# PD.net
KiCad netlist of a schematic drawn in Altium Designer
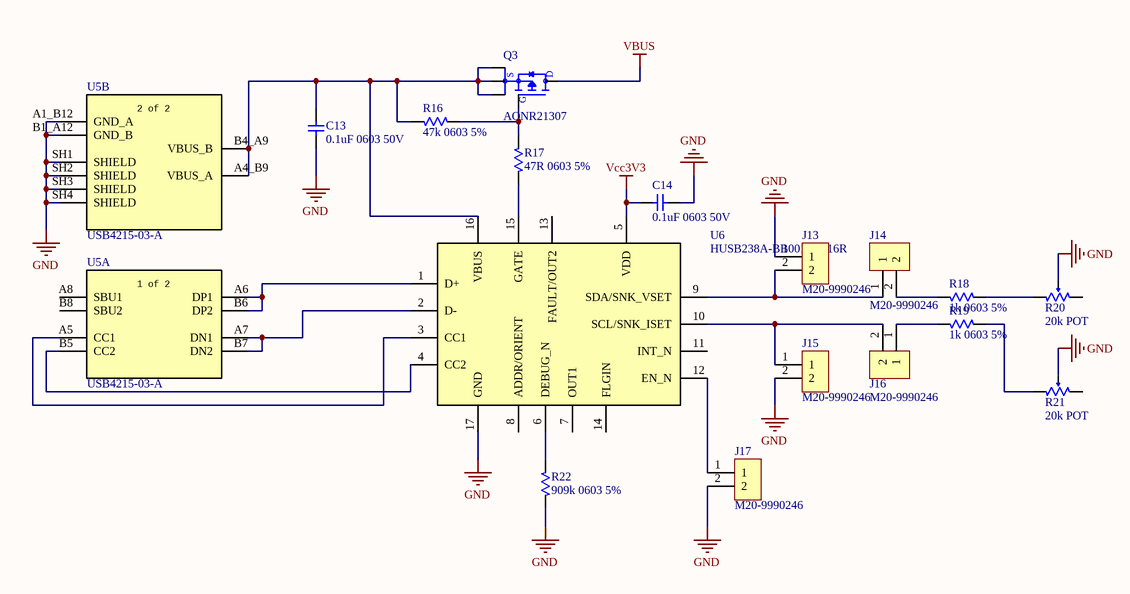
[diagram p0: PD.SchDoc]

(export (version "E")
  (design (tool "Eeschema 10.0.6"))
  (components
    (comp (ref "C13")
      (value "0.1uF 0603 50V")
      (footprint "CAP_0603")
      (description "50V 0.1uF (100nF) X7R ±10% 0603 Multilayer Ceramic Capacitors MLCC - SMD/SMT ROHS")
      (fields
        (field (name "MANUFACTURER PART NUMBER") "CL10B104KB8NNNC")
        (field (name "JLCPCB PART NUMBER") "C1591")
      )
      (libsource (lib "Amperry") (part "Capacitor"))
    )
    (comp (ref "C14")
      (value "0.1uF 0603 50V")
      (footprint "CAP_0603")
      (description "50V 0.1uF (100nF) X7R ±10% 0603 Multilayer Ceramic Capacitors MLCC - SMD/SMT ROHS")
      (fields
        (field (name "MANUFACTURER PART NUMBER") "CL10B104KB8NNNC")
        (field (name "JLCPCB PART NUMBER") "C1591")
      )
      (libsource (lib "Amperry") (part "Capacitor"))
    )
    (comp (ref "J13")
      (value "M20-9990246")
      (footprint "Header_Male_1x2_2.54mm")
      (description "Header Male 1x2 2.54mm")
      (fields (field (name "JLCPCB PART NUMBER") "C90288") (field (name "MANUFACTURER") "Harwin"))
      (libsource (lib "Amperry") (part "Header_Male_1x2"))
    )
    (comp (ref "J14")
      (value "M20-9990246")
      (footprint "Header_Male_1x2_2.54mm")
      (description "Header Male 1x2 2.54mm")
      (fields (field (name "JLCPCB PART NUMBER") "C90288") (field (name "MANUFACTURER") "Harwin"))
      (libsource (lib "") (part "Header_Male_1x2_1"))
    )
    (comp (ref "J15")
      (value "M20-9990246")
      (footprint "Header_Male_1x2_2.54mm")
      (description "Header Male 1x2 2.54mm")
      (fields (field (name "JLCPCB PART NUMBER") "C90288") (field (name "MANUFACTURER") "Harwin"))
      (libsource (lib "Amperry") (part "Header_Male_1x2"))
    )
    (comp (ref "J16")
      (value "M20-9990246")
      (footprint "Header_Male_1x2_2.54mm")
      (description "Header Male 1x2 2.54mm")
      (fields (field (name "JLCPCB PART NUMBER") "C90288") (field (name "MANUFACTURER") "Harwin"))
      (libsource (lib "") (part "Header_Male_1x2_2"))
    )
    (comp (ref "J17")
      (value "M20-9990246")
      (footprint "Header_Male_1x2_2.54mm")
      (description "Header Male 1x2 2.54mm")
      (fields (field (name "JLCPCB PART NUMBER") "C90288") (field (name "MANUFACTURER") "Harwin"))
      (libsource (lib "Amperry") (part "Header_Male_1x2"))
    )
    (comp (ref "Q3")
      (value "AONR21307")
      (footprint "DFN 3x3 EP")
      (description "P-CHANNEL MOSFET 30V 24A 8DFN")
      (fields
        (field (name "JLCPCB PART NUMBER") "C3277813")
        (field (name "MANUFACTURER") "Alpha & Omega Semiconductor")
      )
      (libsource (lib "Amperry") (part "AONR21307"))
    )
    (comp (ref "R16")
      (value "47k 0603 5%")
      (footprint "RES_0603")
      (description "47k Ohm 0603 5% Chip Resistor SMD")
      (fields (field (name "JLCPCB PART NUMBER") "C25819") (field (name "TOLERANCE") "5%"))
      (libsource (lib "Amperry") (part "Resistor"))
    )
    (comp (ref "R17")
      (value "47R 0603 5%")
      (footprint "RES_0603")
      (description "47 Ohm 0603 5% Chip Resistor SMD")
      (fields (field (name "TOLERANCE") "5%") (field (name "JLCPCB PART NUMBER") "C1186"))
      (libsource (lib "Amperry") (part "Resistor"))
    )
    (comp (ref "R18")
      (value "1k 0603 5%")
      (footprint "RES_0603")
      (description "1k 0603 5% Chip Resistor SMD")
      (fields (field (name "JLCPCB PART NUMBER") "C14676") (field (name "TOLERANCE") "5%"))
      (libsource (lib "Amperry") (part "Resistor"))
    )
    (comp (ref "R19")
      (value "1k 0603 5%")
      (footprint "RES_0603")
      (description "1k 0603 5% Chip Resistor SMD")
      (fields (field (name "JLCPCB PART NUMBER") "C14676") (field (name "TOLERANCE") "5%"))
      (libsource (lib "Amperry") (part "Resistor"))
    )
    (comp (ref "R20")
      (value "20k POT")
      (footprint "TRIM_3296W-1-203LF")
      (description "20k Ohm TH Trimmer Potentiometer")
      (fields (field (name "MANUFACTURER") "Bourns") (field (name "JLCPCB PART NUMBER") "C34845"))
      (libsource (lib "Amperry") (part "Resistor Variable"))
    )
    (comp (ref "R21")
      (value "20k POT")
      (footprint "TRIM_3296W-1-203LF")
      (description "20k Ohm TH Trimmer Potentiometer")
      (fields (field (name "MANUFACTURER") "Bourns") (field (name "JLCPCB PART NUMBER") "C34845"))
      (libsource (lib "Amperry") (part "Resistor Variable"))
    )
    (comp (ref "R22")
      (value "909k 0603 5%")
      (footprint "RES_0603")
      (description "909k Ohm 0603 1% Chip Resistor SMD")
      (fields
        (field (name "MANUFACTURER PART NUMBER") "0603WAF9093T5E")
        (field (name "JLCPCB PART NUMBER") "C23262")
      )
      (libsource (lib "Amperry") (part "Resistor"))
    )
    (comp (ref "U5")
      (value "USB4215-03-A")
      (footprint "USB4215-03-A")
      (description "USB-C, 12+4 Contacts 16POS Rohs Compliant: Yes")
      (fields
        (field (name "JLCPCB PART NUMBER") "C165948")
        (field (name "MANUFACTURER") "Global Connector Technology")
      )
      (libsource (lib "Amperry") (part "USB-C 16P"))
    )
    (comp (ref "U6")
      (value "HUSB238A-BB001-QN16R")
      (footprint "QFN-16")
      (description "USB PD Controller")
      (fields (field (name "JLCPCB PART NUMBER") "C24833806"))
      (libsource (lib "Amperry") (part "HUSB238A-BB001-QN16R"))
    )
  )
  (nets
    (net (code "1") (name "GND") (class "Default")
      (node (ref "C13") (pin "1") (pinfunction "1_1") (pintype "passive"))
      (node (ref "C14") (pin "2") (pinfunction "2_2") (pintype "passive"))
      (node (ref "J13") (pin "1") (pinfunction "1_1") (pintype "passive"))
      (node (ref "J15") (pin "2") (pinfunction "2_2") (pintype "passive"))
      (node (ref "J17") (pin "2") (pinfunction "2_2") (pintype "passive"))
      (node (ref "R20") (pin "2") (pinfunction "2_2") (pintype "passive"))
      (node (ref "R21") (pin "2") (pinfunction "2_2") (pintype "passive"))
      (node (ref "R22") (pin "1") (pinfunction "1_1") (pintype "passive"))
      (node (ref "U5") (pin "A1_B12") (pinfunction "GND_A_A1_B12") (pintype "power_in"))
      (node (ref "U5") (pin "B1_A12") (pinfunction "GND_B_B1_A12") (pintype "power_in"))
      (node (ref "U5") (pin "SH1") (pinfunction "SHIELD_SH1") (pintype "passive"))
      (node (ref "U5") (pin "SH2") (pinfunction "SHIELD_SH2") (pintype "passive"))
      (node (ref "U5") (pin "SH3") (pinfunction "SHIELD_SH3") (pintype "passive"))
      (node (ref "U5") (pin "SH4") (pinfunction "SHIELD_SH4") (pintype "passive"))
      (node (ref "U6") (pin "17") (pinfunction "GND_17") (pintype "passive"))
    )
    (net (code "2") (name "Net-(J14-Pad2)") (class "Default")
      (node (ref "J14") (pin "2") (pinfunction "2_2") (pintype "passive"))
      (node (ref "R18") (pin "1") (pinfunction "1_1") (pintype "passive"))
    )
    (net (code "3") (name "Net-(J16-Pad1)") (class "Default")
      (node (ref "J16") (pin "1") (pinfunction "1_1") (pintype "passive"))
      (node (ref "R19") (pin "1") (pinfunction "1_1") (pintype "passive"))
    )
    (net (code "4") (name "Net-(Q3-G)") (class "Default")
      (node (ref "Q3") (pin "4") (pinfunction "G_4") (pintype "passive"))
      (node (ref "R16") (pin "2") (pinfunction "2_2") (pintype "passive"))
      (node (ref "R17") (pin "2") (pinfunction "2_2") (pintype "passive"))
    )
    (net (code "5") (name "Net-(Q3-S1)") (class "Default")
      (node (ref "C13") (pin "2") (pinfunction "2_2") (pintype "passive"))
      (node (ref "Q3") (pin "1") (pinfunction "S1_1") (pintype "passive"))
      (node (ref "Q3") (pin "2") (pinfunction "S2_2") (pintype "passive"))
      (node (ref "Q3") (pin "3") (pinfunction "S3_3") (pintype "passive"))
      (node (ref "R16") (pin "1") (pinfunction "1_1") (pintype "passive"))
      (node (ref "U5") (pin "A4_B9") (pinfunction "VBUS_A_A4_B9") (pintype "power_in"))
      (node (ref "U5") (pin "B4_A9") (pinfunction "VBUS_B_B4_A9") (pintype "power_in"))
      (node (ref "U6") (pin "16") (pinfunction "VBUS_16") (pintype "passive"))
    )
    (net (code "6") (name "Net-(R18-Pad2)") (class "Default")
      (node (ref "R18") (pin "2") (pinfunction "2_2") (pintype "passive"))
      (node (ref "R20") (pin "1") (pinfunction "1_1") (pintype "passive"))
    )
    (net (code "7") (name "Net-(R19-Pad2)") (class "Default")
      (node (ref "R19") (pin "2") (pinfunction "2_2") (pintype "passive"))
      (node (ref "R21") (pin "1") (pinfunction "1_1") (pintype "passive"))
    )
    (net (code "8") (name "Net-(U5A-CC1)") (class "Default")
      (node (ref "U5") (pin "A5") (pinfunction "CC1_A5") (pintype "passive"))
      (node (ref "U6") (pin "3") (pinfunction "CC1_3") (pintype "passive"))
    )
    (net (code "9") (name "Net-(U5A-CC2)") (class "Default")
      (node (ref "U5") (pin "B5") (pinfunction "CC2_B5") (pintype "passive"))
      (node (ref "U6") (pin "4") (pinfunction "CC2_4") (pintype "passive"))
    )
    (net (code "10") (name "Net-(U5A-DN1)") (class "Default")
      (node (ref "U5") (pin "A7") (pinfunction "DN1_A7") (pintype "passive"))
      (node (ref "U5") (pin "B7") (pinfunction "DN2_B7") (pintype "passive"))
      (node (ref "U6") (pin "2") (pinfunction "D-_2") (pintype "passive"))
    )
    (net (code "11") (name "Net-(U5A-DP1)") (class "Default")
      (node (ref "U5") (pin "A6") (pinfunction "DP1_A6") (pintype "passive"))
      (node (ref "U5") (pin "B6") (pinfunction "DP2_B6") (pintype "passive"))
      (node (ref "U6") (pin "1") (pinfunction "D+_1") (pintype "passive"))
    )
    (net (code "12") (name "Net-(U6-DEBUG_N)") (class "Default")
      (node (ref "R22") (pin "2") (pinfunction "2_2") (pintype "passive"))
      (node (ref "U6") (pin "6") (pinfunction "DEBUG_N_6") (pintype "passive"))
    )
    (net (code "13") (name "Net-(U6-EN_N)") (class "Default")
      (node (ref "J17") (pin "1") (pinfunction "1_1") (pintype "passive"))
      (node (ref "U6") (pin "12") (pinfunction "EN_N_12") (pintype "passive"))
    )
    (net (code "14") (name "Net-(U6-GATE)") (class "Default")
      (node (ref "R17") (pin "1") (pinfunction "1_1") (pintype "passive"))
      (node (ref "U6") (pin "15") (pinfunction "GATE_15") (pintype "passive"))
    )
    (net (code "15") (name "Net-(U6-SCL{slash}SNK_ISET)") (class "Default")
      (node (ref "J15") (pin "1") (pinfunction "1_1") (pintype "passive"))
      (node (ref "J16") (pin "2") (pinfunction "2_2") (pintype "passive"))
      (node (ref "U6") (pin "10") (pinfunction "SCL/SNK_ISET_10") (pintype "passive"))
    )
    (net (code "16") (name "Net-(U6-SDA{slash}SNK_VSET)") (class "Default")
      (node (ref "J13") (pin "2") (pinfunction "2_2") (pintype "passive"))
      (node (ref "J14") (pin "1") (pinfunction "1_1") (pintype "passive"))
      (node (ref "U6") (pin "9") (pinfunction "SDA/SNK_VSET_9") (pintype "passive"))
    )
    (net (code "17") (name "VBUS") (class "Default")
      (node (ref "Q3") (pin "5_6_7_8") (pinfunction "D_5_6_7_8") (pintype "passive"))
    )
    (net (code "18") (name "Vcc3V3") (class "Default")
      (node (ref "C14") (pin "1") (pinfunction "1_1") (pintype "passive"))
      (node (ref "U6") (pin "5") (pinfunction "VDD_5") (pintype "passive"))
    )
    (net (code "19") (name "unconnected-(R20-Pad3)") (class "Default")
      (node (ref "R20") (pin "3") (pinfunction "3_3") (pintype "passive"))
    )
    (net (code "20") (name "unconnected-(R21-Pad3)") (class "Default")
      (node (ref "R21") (pin "3") (pinfunction "3_3") (pintype "passive"))
    )
    (net (code "21") (name "unconnected-(U5A-SBU1-PadA8)") (class "Default")
      (node (ref "U5") (pin "A8") (pinfunction "SBU1_A8") (pintype "passive"))
    )
    (net (code "22") (name "unconnected-(U5A-SBU2-PadB8)") (class "Default")
      (node (ref "U5") (pin "B8") (pinfunction "SBU2_B8") (pintype "passive"))
    )
    (net (code "23") (name "unconnected-(U6-ADDR{slash}ORIENT-Pad8)") (class "Default")
      (node (ref "U6") (pin "8") (pinfunction "ADDR/ORIENT_8") (pintype "passive"))
    )
    (net (code "24") (name "unconnected-(U6-FAULT{slash}OUT2-Pad13)") (class "Default")
      (node (ref "U6") (pin "13") (pinfunction "FAULT/OUT2_13") (pintype "passive"))
    )
    (net (code "25") (name "unconnected-(U6-FLGIN-Pad14)") (class "Default")
      (node (ref "U6") (pin "14") (pinfunction "FLGIN_14") (pintype "passive"))
    )
    (net (code "26") (name "unconnected-(U6-INT_N-Pad11)") (class "Default")
      (node (ref "U6") (pin "11") (pinfunction "INT_N_11") (pintype "passive"))
    )
    (net (code "27") (name "unconnected-(U6-OUT1-Pad7)") (class "Default")
      (node (ref "U6") (pin "7") (pinfunction "OUT1_7") (pintype "passive"))
    )
  )
)
